# PowerPath.net
KiCad netlist of a schematic drawn in Altium Designer
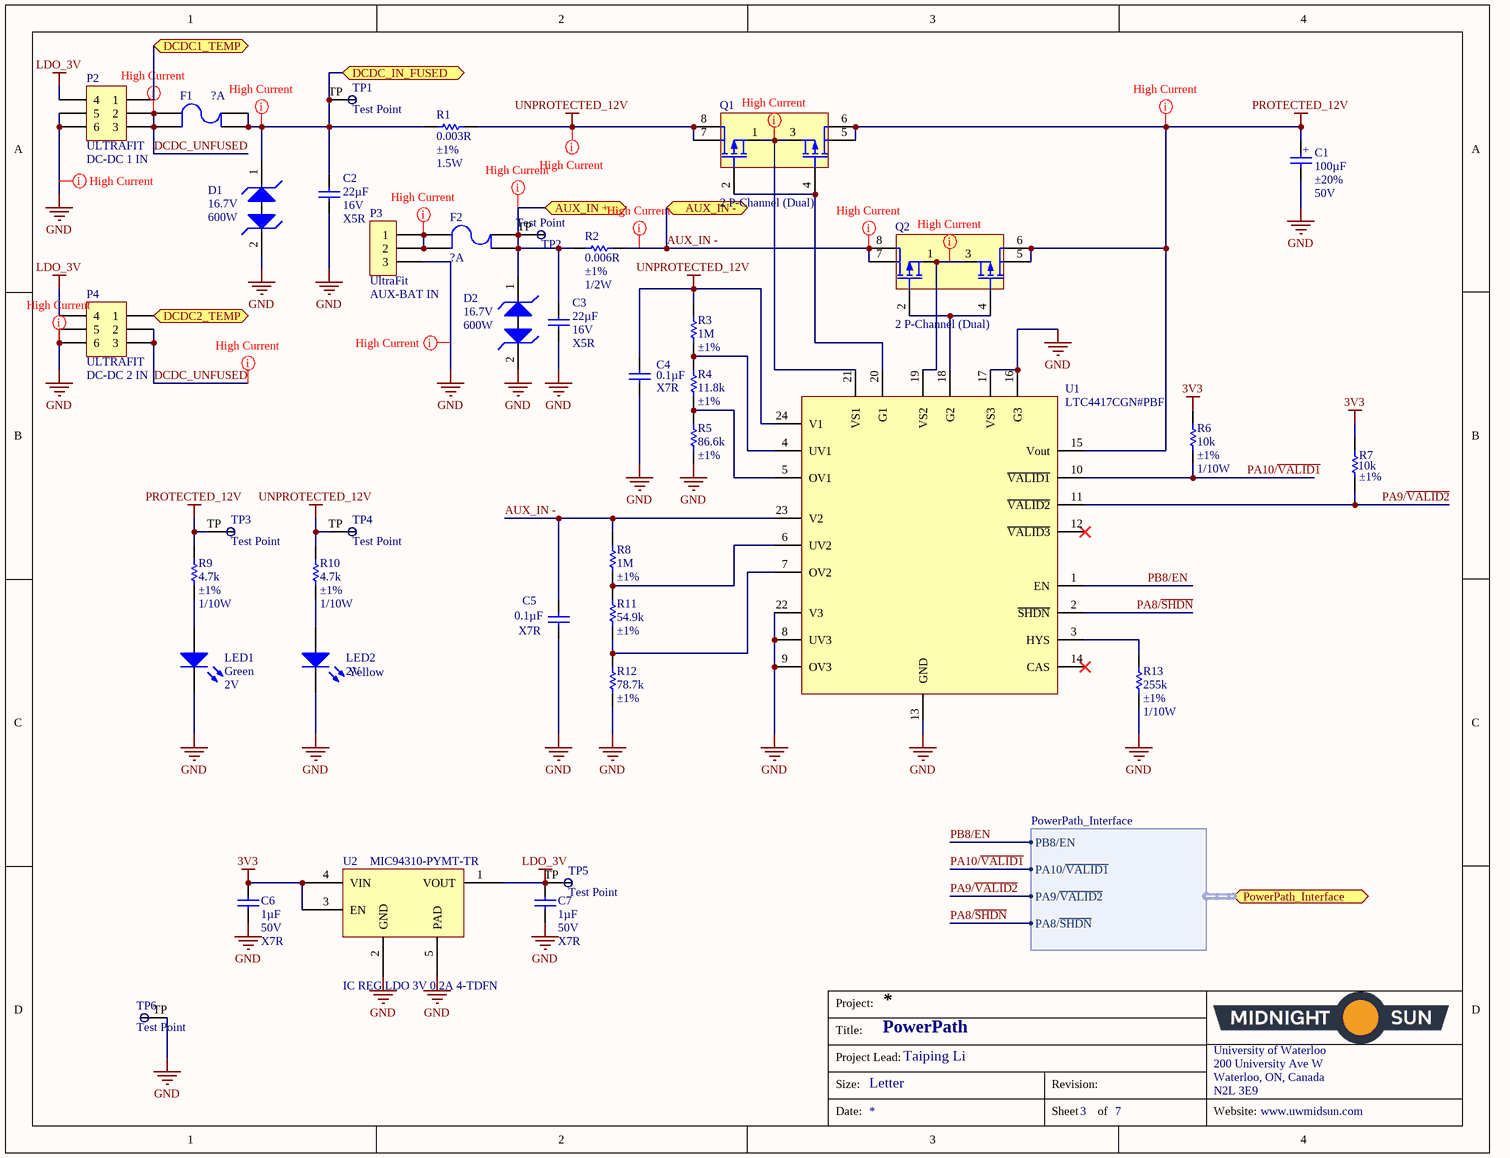
[diagram p0: PowerPath.SchDoc]

(export (version "E")
  (design (tool "Eeschema 10.0.6"))
  (components
    (comp (ref "C1")
      (value "CAP ALUM 100UF 20% 50V RADIAL")
      (footprint "CAP ALUM 100UF 50V")
      (description "100µF 50V Aluminum Capacitors Radial, Can 74 mOhm @ 100kHz 3000 Hrs @ 105°C")
      (fields
        (field (name "TOLERANCE") "±20%")
        (field (name "CAPACITANCE") "100µF")
        (field (name "VOLTAGE RATING") "50V")
      )
      (libsource (lib "Schematic Diagrams") (part "CAP ALUM 100UF 20% 50V RADIAL"))
    )
    (comp (ref "C2")
      (value "CAP CER 22UF 16V ±20% X5R 1210")
      (footprint "CAP, 1210")
      (description "22µF ±20% 16V Ceramic Capacitor X5R 1210 (3225 Metric)")
      (fields
        (field (name "TOLERANCE") "±20%")
        (field (name "CAPACITANCE") "22µF")
        (field (name "VOLTAGE") "16V")
        (field (name "TEMPERATURE COEFFICIENT") "X5R")
      )
      (libsource (lib "Schematic Diagrams") (part "CAP CER 22UF 16V ±20% X5R 1210"))
    )
    (comp (ref "C3")
      (value "CAP CER 22UF 16V ±20% X5R 1210")
      (footprint "CAP, 1210")
      (description "22µF ±20% 16V Ceramic Capacitor X5R 1210 (3225 Metric)")
      (fields
        (field (name "TOLERANCE") "±20%")
        (field (name "CAPACITANCE") "22µF")
        (field (name "VOLTAGE") "16V")
        (field (name "TEMPERATURE COEFFICIENT") "X5R")
      )
      (libsource (lib "Schematic Diagrams") (part "CAP CER 22UF 16V ±20% X5R 1210"))
    )
    (comp (ref "C4")
      (value "CAP CER 0.1UF 50V 10% X7R 0603")
      (footprint "CAP, 0603")
      (description "0.10µF ±10% 50V Ceramic Capacitor X7R 0603 (1608 Metric)")
      (fields
        (field (name "TOLERANCE") "±10%")
        (field (name "CAPACITANCE") "0.1µF")
        (field (name "TEMPERATURE COEFFICIENT") "X7R")
      )
      (libsource (lib "Schematic Diagrams") (part "CAP CER 0.1UF 50V 10% X7R 0603"))
    )
    (comp (ref "C5")
      (value "CAP CER 0.1UF 50V 10% X7R 0603")
      (footprint "CAP, 0603")
      (description "0.10µF ±10% 50V Ceramic Capacitor X7R 0603 (1608 Metric)")
      (fields
        (field (name "TOLERANCE") "±10%")
        (field (name "CAPACITANCE") "0.1µF")
        (field (name "TEMPERATURE COEFFICIENT") "X7R")
      )
      (libsource (lib "Schematic Diagrams") (part "CAP CER 0.1UF 50V 10% X7R 0603"))
    )
    (comp (ref "C6")
      (value "CAP CER 1UF 50V 10% X7R 0603")
      (footprint "CAP, 0603")
      (description "1µF ±10% 50V Ceramic Capacitor X7R 0603 (1608 Metric)")
      (fields
        (field (name "TOLERANCE") "±10%")
        (field (name "CAPACITANCE") "1µF")
        (field (name "VOLTAGE") "50V")
        (field (name "TEMPERATURE COEFFICIENT") "X7R")
      )
      (libsource (lib "Schematic Diagrams") (part "CAP CER 1UF 50V 10% X7R 0603"))
    )
    (comp (ref "C7")
      (value "CAP CER 1UF 50V 10% X7R 0603")
      (footprint "CAP, 0603")
      (description "1µF ±10% 50V Ceramic Capacitor X7R 0603 (1608 Metric)")
      (fields
        (field (name "TOLERANCE") "±10%")
        (field (name "CAPACITANCE") "1µF")
        (field (name "VOLTAGE") "50V")
        (field (name "TEMPERATURE COEFFICIENT") "X7R")
      )
      (libsource (lib "Schematic Diagrams") (part "CAP CER 1UF 50V 10% X7R 0603"))
    )
    (comp (ref "D1")
      (value "DIODE TVS 15VWM 24.4VC DO-214AA (SMB)")
      (footprint "DO-214AA Diode")
      (description "TVS DIODE 15VWM 24.4VC SMB")
      (fields (field (name "VOLTAGE - BREAKDOWN (MIN)") "16.7V") (field (name "POWER - PEAK PULSE") "600W"))
      (libsource (lib "Schematic Diagrams") (part "DIODE TVS 15VWM 24.4VC DO-214AA (SMB)"))
    )
    (comp (ref "D2")
      (value "DIODE TVS 15VWM 24.4VC DO-214AA (SMB)")
      (footprint "DO-214AA Diode")
      (description "TVS DIODE 15VWM 24.4VC SMB")
      (fields (field (name "VOLTAGE - BREAKDOWN (MIN)") "16.7V") (field (name "POWER - PEAK PULSE") "600W"))
      (libsource (lib "Schematic Diagrams") (part "DIODE TVS 15VWM 24.4VC DO-214AA (SMB)"))
    )
    (comp (ref "F1")
      (value "?A")
      (footprint "FUSE ATO/ATC FUSE HOLDER")
      (description "Fuse Block 30A 500V 1 Circuit Blade PCB")
      (fields (field (name "VOLTAGE") "500V"))
      (libsource (lib "Schematic Diagrams") (part "FUSE ATO FUSE HOLDER"))
    )
    (comp (ref "F2")
      (value "?A")
      (footprint "FUSE ATO/ATC FUSE HOLDER")
      (description "Fuse Block 30A 500V 1 Circuit Blade PCB")
      (fields (field (name "VOLTAGE") "500V"))
      (libsource (lib "Schematic Diagrams") (part "FUSE ATO FUSE HOLDER"))
    )
    (comp (ref "LED1")
      (value "LED GREEN CLEAR 2V 0603")
      (footprint "LED_0603")
      (description "Green 572nm LED Indication - Discrete 2V 0603 (1608 Metric)")
      (fields
        (field (name "COLOR") "Green")
        (field (name "VOLTAGE - FORWARD (VF) (TYP)") "2V")
        (field (name "MANUFACTURER") "Wurth Electronics Inc.")
        (field (name "MANUFACTURER PART NUMBER") "150060VS75000")
      )
      (libsource (lib "Schematic Diagrams") (part "LED GREEN CLEAR 2V 0603"))
    )
    (comp (ref "LED2")
      (value "LED YELLOW CLEAR 2.1V 0603")
      (footprint "LED_0603")
      (description "Yellow 590nm LED Indication - Discrete 2V 0603 (1608 Metric)")
      (fields
        (field (name "VOLTAGE - FORWARD (VF) (TYP)") "2V")
        (field (name "MANUFACTURER") "Wurth Electronics Inc.")
        (field (name "MANUFACTURER PART NUMBER") "150060YS75000")
      )
      (libsource (lib "Schematic Diagrams") (part "LED YELLOW CLEAR 2.1V 0603"))
    )
    (comp (ref "P2")
      (value "CONN 6POS ULTRA-FIT 0.138\"")
      (footprint "CONN, 6POS ULTRA-FIT")
      (description "6 Positions Header Connector 0.138\" (3.50mm) Through Hole Tin")
      (fields (field (name "VOLTAGE") "400V") (field (name "SERIES") "ULTRAFIT"))
      (libsource (lib "Schematic Diagrams") (part "CONN 6POS ULTRA-FIT 0.138{dblquote}"))
    )
    (comp (ref "P3")
      (value "CONN 3POS ULTRA-FIT 0.138\"")
      (description "3 Positions Header Connector 0.138\" (3.50mm) Through Hole Tin")
      (fields (field (name "VOLTAGE") "400V") (field (name "SERIES") "UltraFit"))
      (libsource (lib "Schematic Diagrams") (part "CONN 3POS ULTRA-FIT 0.138{dblquote}"))
    )
    (comp (ref "P4")
      (value "CONN 6POS ULTRA-FIT 0.138\"")
      (footprint "CONN, 6POS ULTRA-FIT")
      (description "6 Positions Header Connector 0.138\" (3.50mm) Through Hole Tin")
      (fields (field (name "VOLTAGE") "400V") (field (name "SERIES") "ULTRAFIT"))
      (libsource (lib "Schematic Diagrams") (part "CONN 6POS ULTRA-FIT 0.138{dblquote}"))
    )
    (comp (ref "Q1")
      (value "MOSFET P-CH DUAL 30V 60A PPAK SO-8")
      (footprint "MOSFET 2P-CH 30V 60A PPAK SO-8")
      (description "Mosfet Array 2 P-Channel (Dual) 30V 60A 46W Surface Mount PowerPAK® SO-8 Dual")
      (fields (field (name "FET TYPE") "2 P-Channel (Dual)"))
      (libsource (lib "Schematic Diagrams") (part "MOSFET P-CH DUAL 30V 60A PPAK SO-8"))
    )
    (comp (ref "Q2")
      (value "MOSFET P-CH DUAL 30V 60A PPAK SO-8")
      (footprint "MOSFET 2P-CH 30V 60A PPAK SO-8")
      (description "Mosfet Array 2 P-Channel (Dual) 30V 60A 46W Surface Mount PowerPAK® SO-8 Dual")
      (fields (field (name "FET TYPE") "2 P-Channel (Dual)"))
      (libsource (lib "Schematic Diagrams") (part "MOSFET P-CH DUAL 30V 60A PPAK SO-8"))
    )
    (comp (ref "R1")
      (value "RES 0.003 OHM 1% 1.5W 2010")
      (footprint "RES 2010")
      (description "0.003 Ohm ±1% 1.5W Chip Resistor 2010 (5025 Metric) Current Sense, Moisture Resistant Metal Foil")
      (fields
        (field (name "RESISTANCE (OHMS)") "0.003R")
        (field (name "TOLERANCE") "±1%")
        (field (name "POWER (WATTS)") "1.5W")
      )
      (libsource (lib "Schematic Diagrams") (part "RES 0.003 OHM 1% 1.5W 2010"))
    )
    (comp (ref "R2")
      (value "RES 0.006 OHM 1% 1/2W 1206")
      (footprint "RES 1206")
      (fields
        (field (name "MANUFACTURER") "Panasonic Electronic Components")
        (field (name "MANUFACTURER PART NUMBER") "ERJ-MP2KF6M0U")
        (field (name "RESISTANCE (OHMS)") "0.006R")
        (field (name "TOLERANCE") "±1%")
        (field (name "POWER (WATTS)") "1/2W")
      )
      (libsource (lib "Schematic Diagrams") (part "RES 0.006 OHM 1% 1/2W 1206"))
    )
    (comp (ref "R3")
      (value "RES 1M OHM 1% 1/10W 0603")
      (footprint "RES, 0603")
      (description "1M Ohm ±1% 0.1W, 1/10W Chip Resistor 0603 (1608 Metric) Moisture Resistant Thick Film")
      (fields (field (name "RESISTANCE (OHMS)") "1M") (field (name "TOLERANCE") "±1%"))
      (libsource (lib "Schematic Diagrams") (part "RES 1M OHM 1% 1/10W 0603"))
    )
    (comp (ref "R4")
      (value "RES 11.8K OHM 1% 1/10W 0603")
      (footprint "RES, 0603")
      (description "11.8k Ohm ±1% 0.1W, 1/10W Chip Resistor 0603 (1608 Metric) Moisture Resistant Thick Film")
      (fields
        (field (name "MANUFACTURER") "Yageo")
        (field (name "MANUFACTURER PART NUMBER") "RC0603FR-0711K8L")
        (field (name "RESISTANCE (OHMS)") "11.8k")
        (field (name "TOLERANCE") "±1%")
      )
      (libsource (lib "Schematic Diagrams") (part "RES 11.8K OHM 1% 1/10W 0603"))
    )
    (comp (ref "R5")
      (value "RES 86.6K OHM 1% 1/10W 0603")
      (footprint "RES, 0603")
      (description "86.6k Ohm ±1% 0.1W, 1/10W Chip Resistor 0603 (1608 Metric) Automotive AEC-Q200 Thick Film")
      (fields
        (field (name "MANUFACTURER") "Panasonic Electronic Components")
        (field (name "MANUFACTURER PART NUMBER") "ERJ-3EKF8662V")
        (field (name "RESISTANCE (OHMS)") "86.6k")
        (field (name "TOLERANCE") "±1%")
      )
      (libsource (lib "Schematic Diagrams") (part "RES 86.6K OHM 1% 1/10W 0603"))
    )
    (comp (ref "R6")
      (value "RES 10K OHM 1% 1/10W 0603")
      (footprint "RES, 0603")
      (description "RES SMD 10K OHM 1% 1/10W 0603")
      (fields
        (field (name "RESISTANCE") "10k")
        (field (name "TOLERANCE") "±1%")
        (field (name "POWER") "1/10W")
      )
      (libsource (lib "Schematic Diagrams") (part "RES 10K OHM 1% 1/10W 0603"))
    )
    (comp (ref "R7")
      (value "RES 10K OHM 1% 1/10W 0603")
      (footprint "RES, 0603")
      (description "RES SMD 10K OHM 1% 1/10W 0603")
      (fields (field (name "RESISTANCE") "10k") (field (name "TOLERANCE") "±1%"))
      (libsource (lib "Schematic Diagrams") (part "RES 10K OHM 1% 1/10W 0603"))
    )
    (comp (ref "R8")
      (value "RES 1M OHM 1% 1/10W 0603")
      (footprint "RES, 0603")
      (description "1M Ohm ±1% 0.1W, 1/10W Chip Resistor 0603 (1608 Metric) Moisture Resistant Thick Film")
      (fields (field (name "RESISTANCE (OHMS)") "1M") (field (name "TOLERANCE") "±1%"))
      (libsource (lib "Schematic Diagrams") (part "RES 1M OHM 1% 1/10W 0603"))
    )
    (comp (ref "R9")
      (value "RES 4.7K OHM 1% 1/10W 0603")
      (footprint "RES, 0603")
      (description "4.7k Ohm ±1% 0.1W, 1/10W Chip Resistor 0603 (1608 Metric) Moisture Resistant Thick Film")
      (fields
        (field (name "RESISTANCE (OHMS)") "4.7k")
        (field (name "TOLERANCE") "±1%")
        (field (name "POWER (WATTS)") "1/10W")
      )
      (libsource (lib "Schematic Diagrams") (part "RES 4.7K OHM 1% 1/10W 0603"))
    )
    (comp (ref "R10")
      (value "RES 4.7K OHM 1% 1/10W 0603")
      (footprint "RES, 0603")
      (description "4.7k Ohm ±1% 0.1W, 1/10W Chip Resistor 0603 (1608 Metric) Moisture Resistant Thick Film")
      (fields
        (field (name "RESISTANCE (OHMS)") "4.7k")
        (field (name "TOLERANCE") "±1%")
        (field (name "POWER (WATTS)") "1/10W")
      )
      (libsource (lib "Schematic Diagrams") (part "RES 4.7K OHM 1% 1/10W 0603"))
    )
    (comp (ref "R11")
      (value "RES 54.9K OHM 1% 1/10W 0603")
      (footprint "RES, 0603")
      (description "54.9k Ohm ±1% 0.1W, 1/10W Chip Resistor 0603 (1608 Metric) Automotive AEC-Q200 Thick Film")
      (fields
        (field (name "MANUFACTURER") "Panasonic Electronic Components")
        (field (name "MANUFACTURER PART NUMBER") "ERJ-3EKF5492V")
        (field (name "RESISTANCE (OHMS)") "54.9k")
        (field (name "TOLERANCE") "±1%")
      )
      (libsource (lib "Schematic Diagrams") (part "RES 54.9K OHM 1% 1/10W 0603"))
    )
    (comp (ref "R12")
      (value "RES 78.7K OHM 1% 1/10W 0603")
      (footprint "RES, 0603")
      (description "78.7k Ohm ±1% 0.1W, 1/10W Chip Resistor 0603 (1608 Metric) Automotive AEC-Q200 Thick Film")
      (fields
        (field (name "MANUFACTURER") "Panasonic Electronic Components")
        (field (name "MANUFACTURER PART NUMBER") "ERJ-3EKF7872V")
        (field (name "RESISTANCE (OHMS)") "78.7k")
        (field (name "TOLERANCE") "±1%")
      )
      (libsource (lib "Schematic Diagrams") (part "RES 78.7K OHM 1% 1/10W 0603"))
    )
    (comp (ref "R13")
      (value "RES 255K OHM 1% 1/10W 0603")
      (footprint "RES, 0603")
      (description "255k Ohm ±1% 0.1W, 1/10W Chip Resistor 0603 (1608 Metric) Moisture Resistant Thick Film")
      (fields
        (field (name "RESISTANCE (OHMS)") "255k")
        (field (name "TOLERANCE") "±1%")
        (field (name "POWER (WATTS)") "1/10W")
      )
      (libsource (lib "Schematic Diagrams") (part "RES 255K OHM 1% 1/10W 0603"))
    )
    (comp (ref "TP1")
      (value "Test Point")
      (footprint "Test Point")
      (libsource (lib "Schematic Diagrams") (part "Test Point"))
    )
    (comp (ref "TP2")
      (value "Test Point")
      (footprint "Test Point")
      (libsource (lib "Schematic Diagrams") (part "Test Point"))
    )
    (comp (ref "TP3")
      (value "Test Point")
      (footprint "Test Point")
      (libsource (lib "Schematic Diagrams") (part "Test Point"))
    )
    (comp (ref "TP4")
      (value "Test Point")
      (footprint "Test Point")
      (libsource (lib "Schematic Diagrams") (part "Test Point"))
    )
    (comp (ref "TP5")
      (value "Test Point")
      (footprint "Test Point")
      (libsource (lib "Schematic Diagrams") (part "Test Point"))
    )
    (comp (ref "TP6")
      (value "Test Point")
      (footprint "Test Point")
      (libsource (lib "Schematic Diagrams") (part "Test Point"))
    )
    (comp (ref "U1")
      (value "IC OR CONTROLLER SOURCE SELECT 24SSOP")
      (footprint "IC OR CTRLR SRC SELECT 24SSOP")
      (description "OR Controller Source Selector Switch P-Channel 3:1 24-SSOP")
      (fields (field (name "MANUFACTURER PART NUMBER 1") "LTC4417CGN#PBF"))
      (libsource (lib "Schematic Diagrams") (part "IC OR CONTROLLER SOURCE SELECT 24SSOP"))
    )
    (comp (ref "U2")
      (value "IC REG LDO 3V 0.2A 4-TDFN")
      (footprint "IC REG LDO 3V 0.2A 4-TDFN")
      (fields
        (field (name "MANUFACTURER") "Microchip Technology")
        (field (name "MANUFACTURER PART NUMBER") "MIC94310-PYMT-TR")
      )
      (libsource (lib "Schematic Diagrams") (part "IC REG LDO 3V 0.2A 4-TDFN"))
    )
  )
  (nets
    (net (code "2") (name "/AUX_IN +") (class "Default")
      (node (ref "C3") (pin "1") (pinfunction "1_1") (pintype "passive"))
      (node (ref "D2") (pin "1") (pinfunction "Cathode1_1") (pintype "passive"))
      (node (ref "F2") (pin "2") (pinfunction "2_2") (pintype "passive"))
      (node (ref "F2") (pin "4") (pinfunction "4_4") (pintype "passive"))
      (node (ref "R2") (pin "1") (pinfunction "1_1") (pintype "passive"))
      (node (ref "TP2") (pin "TP") (pinfunction "1_TP") (pintype "passive"))
    )
    (net (code "3") (name "/AUX_IN -") (class "Default")
      (node (ref "C5") (pin "1") (pinfunction "1_1") (pintype "passive"))
      (node (ref "Q2") (pin "7") (pinfunction "D1_7") (pintype "passive"))
      (node (ref "Q2") (pin "8") (pinfunction "D1_8") (pintype "passive"))
      (node (ref "R2") (pin "2") (pinfunction "2_2") (pintype "passive"))
      (node (ref "R8") (pin "1") (pinfunction "1_1") (pintype "passive"))
      (node (ref "U1") (pin "23") (pinfunction "V2_23") (pintype "passive"))
    )
    (net (code "4") (name "/DCDC1_TEMP") (class "Default")
      (node (ref "P2") (pin "1") (pinfunction "1_1") (pintype "passive"))
    )
    (net (code "5") (name "/DCDC2_TEMP") (class "Default")
      (node (ref "P4") (pin "1") (pinfunction "1_1") (pintype "passive"))
    )
    (net (code "6") (name "/DCDC_IN_FUSED") (class "Default")
      (node (ref "C2") (pin "1") (pinfunction "1_1") (pintype "passive"))
      (node (ref "D1") (pin "1") (pinfunction "Cathode1_1") (pintype "passive"))
      (node (ref "F1") (pin "2") (pinfunction "2_2") (pintype "passive"))
      (node (ref "F1") (pin "4") (pinfunction "4_4") (pintype "passive"))
      (node (ref "R1") (pin "1") (pinfunction "1_1") (pintype "passive"))
      (node (ref "TP1") (pin "TP") (pinfunction "1_TP") (pintype "passive"))
    )
    (net (code "7") (name "/DCDC_UNFUSED") (class "Default")
      (node (ref "F1") (pin "1") (pinfunction "1_1") (pintype "passive"))
      (node (ref "F1") (pin "3") (pinfunction "3_3") (pintype "passive"))
      (node (ref "P2") (pin "2") (pinfunction "2_2") (pintype "passive"))
      (node (ref "P2") (pin "3") (pinfunction "3_3") (pintype "passive"))
      (node (ref "P4") (pin "2") (pinfunction "2_2") (pintype "passive"))
      (node (ref "P4") (pin "3") (pinfunction "3_3") (pintype "passive"))
    )
    (net (code "8") (name "/PA8{slash}~{SHDN}") (class "Default")
      (node (ref "U1") (pin "2") (pinfunction "~{SHDN}_2") (pintype "passive"))
    )
    (net (code "9") (name "/PA9{slash}~{VALID2}") (class "Default")
      (node (ref "R7") (pin "2") (pinfunction "2_2") (pintype "passive"))
      (node (ref "U1") (pin "11") (pinfunction "~{VALID2}_11") (pintype "passive"))
    )
    (net (code "10") (name "/PA10{slash}~{VALID1}") (class "Default")
      (node (ref "R6") (pin "2") (pinfunction "2_2") (pintype "passive"))
      (node (ref "U1") (pin "10") (pinfunction "~{VALID1}_10") (pintype "passive"))
    )
    (net (code "11") (name "/PB8{slash}EN") (class "Default")
      (node (ref "U1") (pin "1") (pinfunction "EN_1") (pintype "passive"))
    )
    (net (code "13") (name "3V3") (class "Default")
      (node (ref "C6") (pin "1") (pinfunction "1_1") (pintype "passive"))
      (node (ref "R6") (pin "1") (pinfunction "1_1") (pintype "passive"))
      (node (ref "R7") (pin "1") (pinfunction "1_1") (pintype "passive"))
      (node (ref "U2") (pin "3") (pinfunction "EN_3") (pintype "passive"))
      (node (ref "U2") (pin "4") (pinfunction "VIN_4") (pintype "passive"))
    )
    (net (code "14") (name "GND") (class "Default")
      (node (ref "C1") (pin "2") (pinfunction "2_2") (pintype "passive"))
      (node (ref "C2") (pin "2") (pinfunction "2_2") (pintype "passive"))
      (node (ref "C3") (pin "2") (pinfunction "2_2") (pintype "passive"))
      (node (ref "C4") (pin "2") (pinfunction "2_2") (pintype "passive"))
      (node (ref "C5") (pin "2") (pinfunction "2_2") (pintype "passive"))
      (node (ref "C6") (pin "2") (pinfunction "2_2") (pintype "passive"))
      (node (ref "C7") (pin "2") (pinfunction "2_2") (pintype "passive"))
      (node (ref "D1") (pin "2") (pinfunction "Cathode2_2") (pintype "passive"))
      (node (ref "D2") (pin "2") (pinfunction "Cathode2_2") (pintype "passive"))
      (node (ref "LED1") (pin "2") (pinfunction "K_2") (pintype "passive"))
      (node (ref "LED2") (pin "2") (pinfunction "K_2") (pintype "passive"))
      (node (ref "P2") (pin "5") (pinfunction "5_5") (pintype "passive"))
      (node (ref "P2") (pin "6") (pinfunction "6_6") (pintype "passive"))
      (node (ref "P3") (pin "3") (pinfunction "3_3") (pintype "passive"))
      (node (ref "P4") (pin "5") (pinfunction "5_5") (pintype "passive"))
      (node (ref "P4") (pin "6") (pinfunction "6_6") (pintype "passive"))
      (node (ref "R12") (pin "2") (pinfunction "2_2") (pintype "passive"))
      (node (ref "R13") (pin "2") (pinfunction "2_2") (pintype "passive"))
      (node (ref "R5") (pin "2") (pinfunction "2_2") (pintype "passive"))
      (node (ref "TP6") (pin "TP") (pinfunction "1_TP") (pintype "passive"))
      (node (ref "U1") (pin "13") (pinfunction "GND_13") (pintype "passive"))
      (node (ref "U1") (pin "16") (pinfunction "G3_16") (pintype "passive"))
      (node (ref "U1") (pin "17") (pinfunction "VS3_17") (pintype "passive"))
      (node (ref "U1") (pin "22") (pinfunction "V3_22") (pintype "passive"))
      (node (ref "U1") (pin "8") (pinfunction "UV3_8") (pintype "passive"))
      (node (ref "U1") (pin "9") (pinfunction "OV3_9") (pintype "passive"))
      (node (ref "U2") (pin "2") (pinfunction "GND_2") (pintype "passive"))
      (node (ref "U2") (pin "5") (pinfunction "PAD_5") (pintype "passive"))
    )
    (net (code "15") (name "LDO_3V") (class "Default")
      (node (ref "C7") (pin "1") (pinfunction "1_1") (pintype "passive"))
      (node (ref "P2") (pin "4") (pinfunction "4_4") (pintype "passive"))
      (node (ref "P4") (pin "4") (pinfunction "4_4") (pintype "passive"))
      (node (ref "TP5") (pin "TP") (pinfunction "1_TP") (pintype "passive"))
      (node (ref "U2") (pin "1") (pinfunction "VOUT_1") (pintype "passive"))
    )
    (net (code "16") (name "Net-(F2-Pad1)") (class "Default")
      (node (ref "F2") (pin "1") (pinfunction "1_1") (pintype "passive"))
      (node (ref "F2") (pin "3") (pinfunction "3_3") (pintype "passive"))
      (node (ref "P3") (pin "1") (pinfunction "1_1") (pintype "passive"))
      (node (ref "P3") (pin "2") (pinfunction "2_2") (pintype "passive"))
    )
    (net (code "17") (name "Net-(LED1-A)") (class "Default")
      (node (ref "LED1") (pin "1") (pinfunction "A_1") (pintype "passive"))
      (node (ref "R9") (pin "2") (pinfunction "2_2") (pintype "passive"))
    )
    (net (code "18") (name "Net-(LED2-A)") (class "Default")
      (node (ref "LED2") (pin "1") (pinfunction "A_1") (pintype "passive"))
      (node (ref "R10") (pin "2") (pinfunction "2_2") (pintype "passive"))
    )
    (net (code "19") (name "Net-(Q1-G1)") (class "Default")
      (node (ref "Q1") (pin "2") (pinfunction "G1_2") (pintype "passive"))
      (node (ref "Q1") (pin "4") (pinfunction "G2_4") (pintype "passive"))
      (node (ref "U1") (pin "20") (pinfunction "G1_20") (pintype "passive"))
    )
    (net (code "20") (name "Net-(Q1-S1)") (class "Default")
      (node (ref "Q1") (pin "1") (pinfunction "S1_1") (pintype "passive"))
      (node (ref "Q1") (pin "3") (pinfunction "S2_3") (pintype "passive"))
      (node (ref "U1") (pin "21") (pinfunction "VS1_21") (pintype "passive"))
    )
    (net (code "21") (name "Net-(Q2-G1)") (class "Default")
      (node (ref "Q2") (pin "2") (pinfunction "G1_2") (pintype "passive"))
      (node (ref "Q2") (pin "4") (pinfunction "G2_4") (pintype "passive"))
      (node (ref "U1") (pin "18") (pinfunction "G2_18") (pintype "passive"))
    )
    (net (code "22") (name "Net-(Q2-S1)") (class "Default")
      (node (ref "Q2") (pin "1") (pinfunction "S1_1") (pintype "passive"))
      (node (ref "Q2") (pin "3") (pinfunction "S2_3") (pintype "passive"))
      (node (ref "U1") (pin "19") (pinfunction "VS2_19") (pintype "passive"))
    )
    (net (code "23") (name "Net-(U1-HYS)") (class "Default")
      (node (ref "R13") (pin "1") (pinfunction "1_1") (pintype "passive"))
      (node (ref "U1") (pin "3") (pinfunction "HYS_3") (pintype "passive"))
    )
    (net (code "24") (name "Net-(U1-OV1)") (class "Default")
      (node (ref "R4") (pin "2") (pinfunction "2_2") (pintype "passive"))
      (node (ref "R5") (pin "1") (pinfunction "1_1") (pintype "passive"))
      (node (ref "U1") (pin "5") (pinfunction "OV1_5") (pintype "passive"))
    )
    (net (code "25") (name "Net-(U1-OV2)") (class "Default")
      (node (ref "R11") (pin "2") (pinfunction "2_2") (pintype "passive"))
      (node (ref "R12") (pin "1") (pinfunction "1_1") (pintype "passive"))
      (node (ref "U1") (pin "7") (pinfunction "OV2_7") (pintype "passive"))
    )
    (net (code "26") (name "Net-(U1-UV1)") (class "Default")
      (node (ref "R3") (pin "2") (pinfunction "2_2") (pintype "passive"))
      (node (ref "R4") (pin "1") (pinfunction "1_1") (pintype "passive"))
      (node (ref "U1") (pin "4") (pinfunction "UV1_4") (pintype "passive"))
    )
    (net (code "27") (name "Net-(U1-UV2)") (class "Default")
      (node (ref "R11") (pin "1") (pinfunction "1_1") (pintype "passive"))
      (node (ref "R8") (pin "2") (pinfunction "2_2") (pintype "passive"))
      (node (ref "U1") (pin "6") (pinfunction "UV2_6") (pintype "passive"))
    )
    (net (code "28") (name "PROTECTED_12V") (class "Default")
      (node (ref "C1") (pin "1") (pinfunction "1_1") (pintype "passive"))
      (node (ref "Q1") (pin "5") (pinfunction "D2_5") (pintype "passive"))
      (node (ref "Q1") (pin "6") (pinfunction "D2_6") (pintype "passive"))
      (node (ref "Q2") (pin "5") (pinfunction "D2_5") (pintype "passive"))
      (node (ref "Q2") (pin "6") (pinfunction "D2_6") (pintype "passive"))
      (node (ref "R9") (pin "1") (pinfunction "1_1") (pintype "passive"))
      (node (ref "TP3") (pin "TP") (pinfunction "1_TP") (pintype "passive"))
      (node (ref "U1") (pin "15") (pinfunction "Vout_15") (pintype "passive"))
    )
    (net (code "29") (name "UNPROTECTED_12V") (class "Default")
      (node (ref "C4") (pin "1") (pinfunction "1_1") (pintype "passive"))
      (node (ref "Q1") (pin "7") (pinfunction "D1_7") (pintype "passive"))
      (node (ref "Q1") (pin "8") (pinfunction "D1_8") (pintype "passive"))
      (node (ref "R1") (pin "2") (pinfunction "2_2") (pintype "passive"))
      (node (ref "R10") (pin "1") (pinfunction "1_1") (pintype "passive"))
      (node (ref "R3") (pin "1") (pinfunction "1_1") (pintype "passive"))
      (node (ref "TP4") (pin "TP") (pinfunction "1_TP") (pintype "passive"))
      (node (ref "U1") (pin "24") (pinfunction "V1_24") (pintype "passive"))
    )
    (net (code "30") (name "unconnected-(U1-CAS-Pad14)") (class "Default")
      (node (ref "U1") (pin "14") (pinfunction "CAS_14") (pintype "passive+no_connect"))
    )
    (net (code "31") (name "unconnected-(U1-~{VALID3}-Pad12)") (class "Default")
      (node (ref "U1") (pin "12") (pinfunction "~{VALID3}_12") (pintype "passive+no_connect"))
    )
  )
)
